# Sheet2.net
KiCad netlist of a schematic drawn in Altium Designer
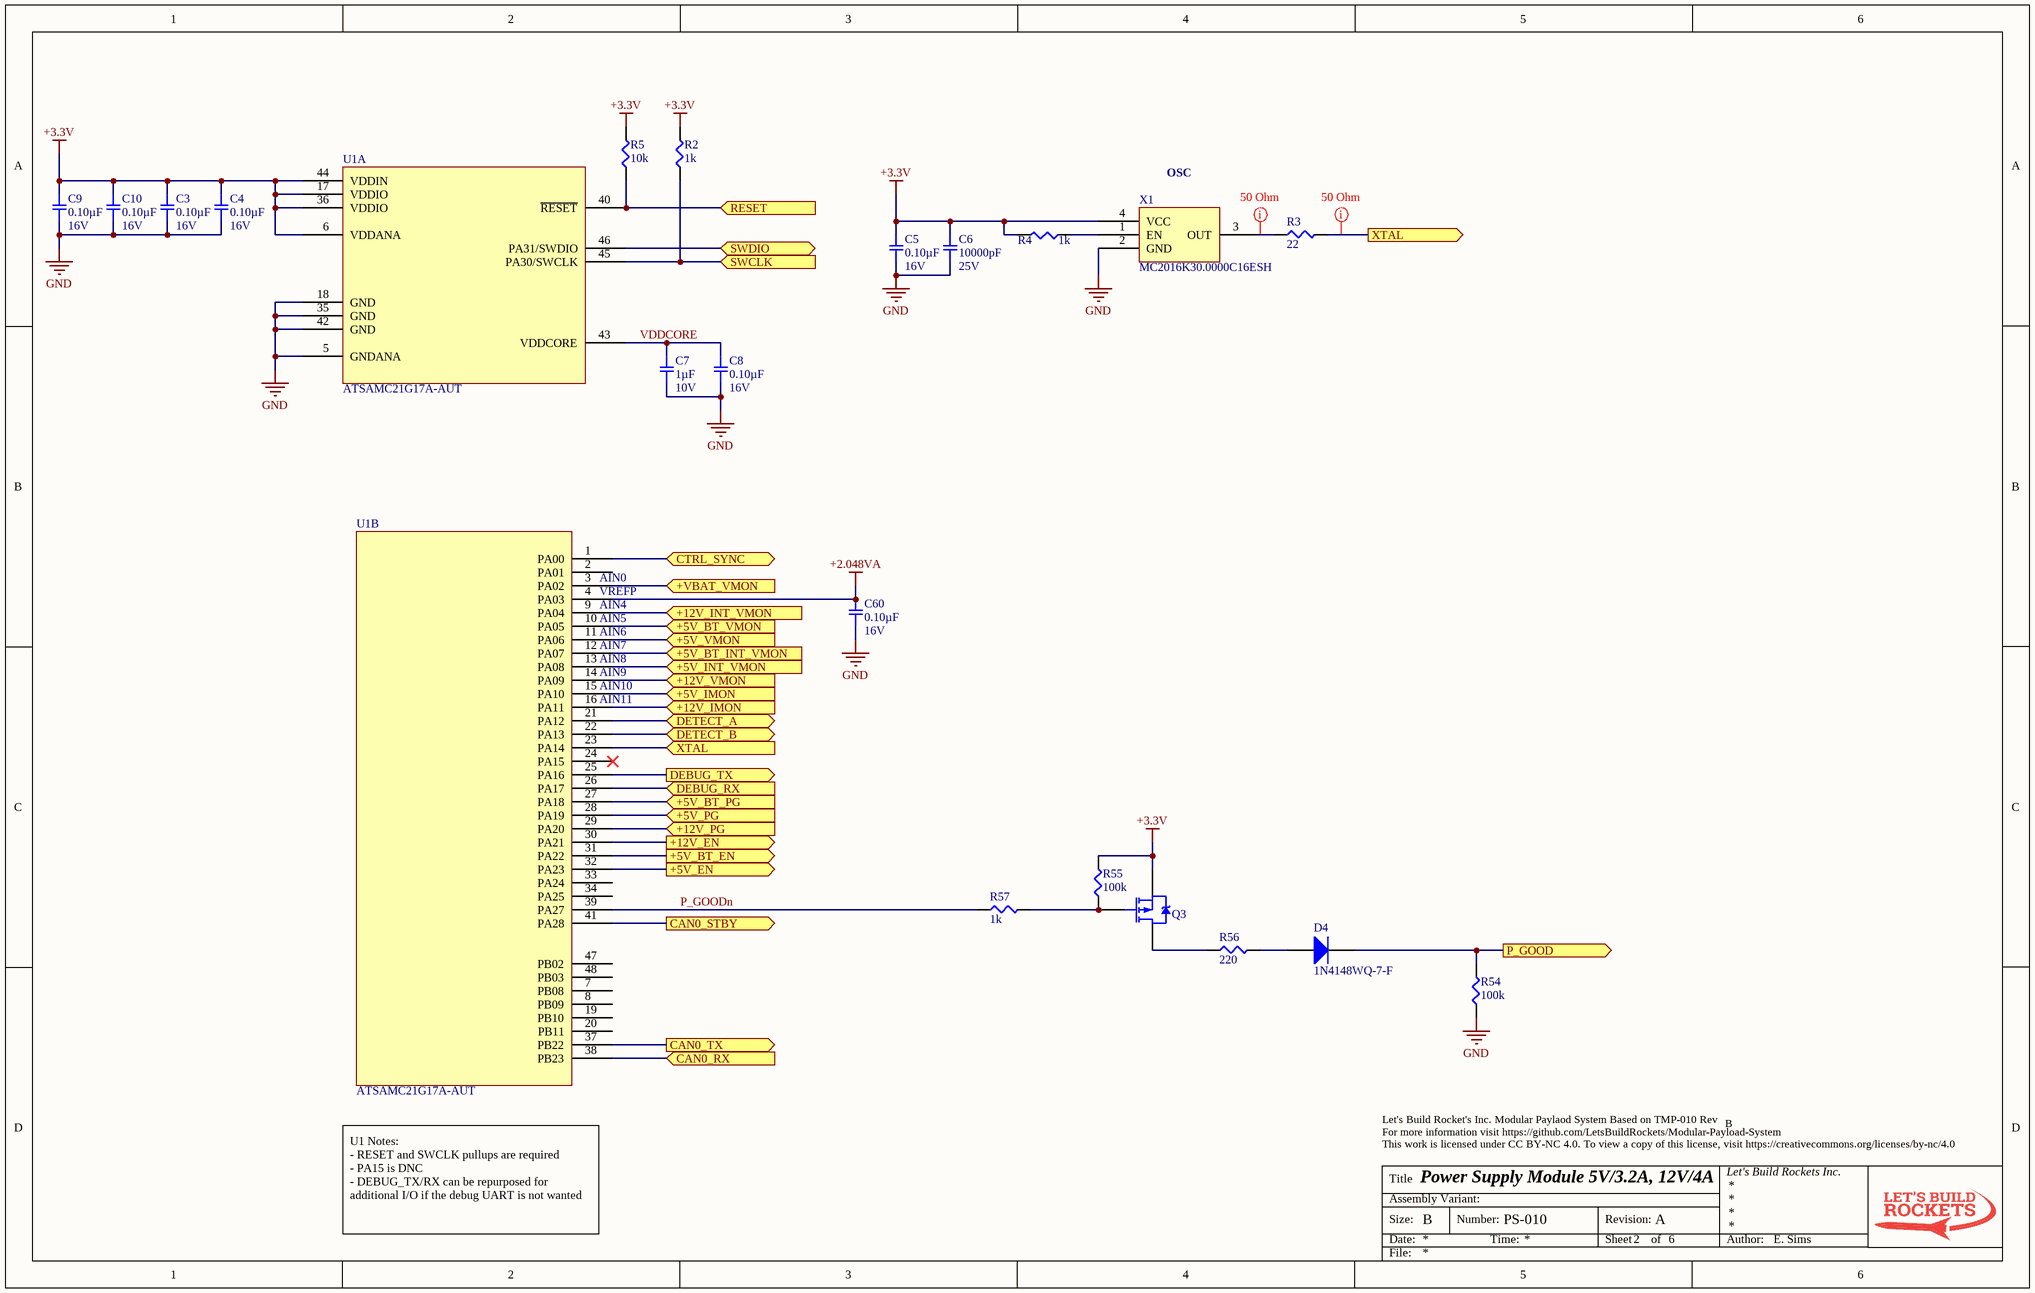
[diagram p0: Sheet2.SchDoc]

(export (version "E")
  (design (tool "Eeschema 10.0.6"))
  (components
    (comp (ref "C3")
      (value "0.10µF")
      (footprint "SMD-0402C")
      (description "CAP CER 0.1UF 16V X7R 0402")
      (fields
        (field (name "DIGI-KEY PART NUMBER") "490-4759-1-ND")
        (field (name "PART NUMBER") "GCM155R71C104KA55D")
        (field (name "VOLTAGE") "16V")
      )
      (libsource (lib "capacitor_murata_0402") (part "GCM155R71C104KA55D"))
    )
    (comp (ref "C4")
      (value "0.10µF")
      (footprint "SMD-0402C")
      (description "CAP CER 0.1UF 16V X7R 0402")
      (fields
        (field (name "DIGI-KEY PART NUMBER") "490-4759-1-ND")
        (field (name "PART NUMBER") "GCM155R71C104KA55D")
        (field (name "VOLTAGE") "16V")
      )
      (libsource (lib "capacitor_murata_0402") (part "GCM155R71C104KA55D"))
    )
    (comp (ref "C5")
      (value "0.10µF")
      (footprint "SMD-0402C")
      (description "CAP CER 0.1UF 16V X7R 0402")
      (fields
        (field (name "DIGI-KEY PART NUMBER") "490-4759-1-ND")
        (field (name "PART NUMBER") "GCM155R71C104KA55D")
        (field (name "VOLTAGE") "16V")
      )
      (libsource (lib "capacitor_murata_0402") (part "GCM155R71C104KA55D"))
    )
    (comp (ref "C6")
      (value "10000pF")
      (footprint "SMD-0402C")
      (description "CAP CER 10000PF 25V X7R 0402")
      (fields
        (field (name "DIGI-KEY PART NUMBER") "490-6043-1-ND")
        (field (name "PART NUMBER") "GCM155R71E103KA37D")
        (field (name "VOLTAGE") "25V")
      )
      (libsource (lib "capacitor_murata_0402") (part "GCM155R71E103KA37D"))
    )
    (comp (ref "C7")
      (value "1µF")
      (footprint "SMD-0402C")
      (description "CAP CER 1UF 10V X7S 0402")
      (fields
        (field (name "DIGI-KEY PART NUMBER") "490-13409-1-ND")
        (field (name "PART NUMBER") "GCM155C71A105KE38D")
        (field (name "VOLTAGE") "10V")
      )
      (libsource (lib "capacitor_murata_0402") (part "GCM155C71A105KE38D"))
    )
    (comp (ref "C8")
      (value "0.10µF")
      (footprint "SMD-0402C")
      (description "CAP CER 0.1UF 16V X7R 0402")
      (fields
        (field (name "DIGI-KEY PART NUMBER") "490-4759-1-ND")
        (field (name "PART NUMBER") "GCM155R71C104KA55D")
        (field (name "VOLTAGE") "16V")
      )
      (libsource (lib "capacitor_murata_0402") (part "GCM155R71C104KA55D"))
    )
    (comp (ref "C9")
      (value "0.10µF")
      (footprint "SMD-0402C")
      (description "CAP CER 0.1UF 16V X7R 0402")
      (fields
        (field (name "DIGI-KEY PART NUMBER") "490-4759-1-ND")
        (field (name "PART NUMBER") "GCM155R71C104KA55D")
        (field (name "VOLTAGE") "16V")
      )
      (libsource (lib "capacitor_murata_0402") (part "GCM155R71C104KA55D"))
    )
    (comp (ref "C10")
      (value "0.10µF")
      (footprint "SMD-0402C")
      (description "CAP CER 0.1UF 16V X7R 0402")
      (fields
        (field (name "DIGI-KEY PART NUMBER") "490-4759-1-ND")
        (field (name "PART NUMBER") "GCM155R71C104KA55D")
        (field (name "VOLTAGE") "16V")
      )
      (libsource (lib "capacitor_murata_0402") (part "GCM155R71C104KA55D"))
    )
    (comp (ref "C60")
      (value "0.10µF")
      (footprint "SMD-0402C")
      (description "CAP CER 0.1UF 16V X7R 0402")
      (fields
        (field (name "DIGI-KEY PART NUMBER") "490-4759-1-ND")
        (field (name "PART NUMBER") "GCM155R71C104KA55D")
        (field (name "VOLTAGE") "16V")
      )
      (libsource (lib "capacitor_murata_0402") (part "GCM155R71C104KA55D"))
    )
    (comp (ref "D4")
      (value "1N4148WQ-7-F")
      (footprint "SOD123")
      (libsource (lib "ModularPayload") (part "1N4148WQ-7-F"))
    )
    (comp (ref "Q3")
      (value "BSS84AK,215")
      (footprint "SOT95P230X110-3N (BSS84)")
      (libsource (lib "ModularPayload") (part "BSS84AK,215"))
    )
    (comp (ref "R2")
      (value "1k")
      (footprint "SMD-0402-RES")
      (description "RES SMD 1K OHM 5% 1/10W 0402")
      (fields (field (name "PART NUMBER") "ERJ-2GEJ102X") (field (name "DIGI-KEY PART NUMBER") "P1.0KJCT-ND"))
      (libsource (lib "Panasonic_ERJ_0402") (part "ERJ-2GEJ102X"))
    )
    (comp (ref "R3")
      (value "22")
      (footprint "SMD-0402-RES")
      (description "RES SMD 22 OHM 1% 1/10W 0402")
      (fields
        (field (name "PART NUMBER") "ERJ-2RKF22R0X")
        (field (name "DIGI-KEY PART NUMBER") "P22.0LCT-ND")
      )
      (libsource (lib "Panasonic_ERJ_0402") (part "ERJ-2RKF22R0X"))
    )
    (comp (ref "R4")
      (value "1k")
      (footprint "SMD-0402-RES")
      (description "RES SMD 1K OHM 5% 1/10W 0402")
      (fields (field (name "PART NUMBER") "ERJ-2GEJ102X") (field (name "DIGI-KEY PART NUMBER") "P1.0KJCT-ND"))
      (libsource (lib "Panasonic_ERJ_0402") (part "ERJ-2GEJ102X"))
    )
    (comp (ref "R5")
      (value "10k")
      (footprint "SMD-0402-RES")
      (description "RES SMD 10K OHM 5% 1/10W 0402")
      (fields (field (name "PART NUMBER") "ERJ-2GEJ103X") (field (name "DIGI-KEY PART NUMBER") "P10KJCT-ND"))
      (libsource (lib "Panasonic_ERJ_0402") (part "ERJ-2GEJ103X"))
    )
    (comp (ref "R54")
      (value "100k")
      (footprint "SMD-0402-RES")
      (description "RES SMD 100K OHM 5% 1/10W 0402")
      (fields (field (name "PART NUMBER") "ERJ-2GEJ104X") (field (name "DIGI-KEY PART NUMBER") "P100KJCT-ND"))
      (libsource (lib "Panasonic_ERJ_0402") (part "ERJ-2GEJ104X"))
    )
    (comp (ref "R55")
      (value "100k")
      (footprint "SMD-0402-RES")
      (description "RES SMD 100K OHM 5% 1/10W 0402")
      (fields (field (name "PART NUMBER") "ERJ-2GEJ104X") (field (name "DIGI-KEY PART NUMBER") "P100KJCT-ND"))
      (libsource (lib "Panasonic_ERJ_0402") (part "ERJ-2GEJ104X"))
    )
    (comp (ref "R56")
      (value "220")
      (footprint "SMD-0402-RES")
      (description "RES SMD 220 OHM 5% 1/10W 0402")
      (fields (field (name "PART NUMBER") "ERJ-2GEJ221X") (field (name "DIGI-KEY PART NUMBER") "P220JCT-ND"))
      (libsource (lib "Panasonic_ERJ_0402") (part "ERJ-2GEJ221X"))
    )
    (comp (ref "R57")
      (value "1k")
      (footprint "SMD-0402-RES")
      (description "RES SMD 1K OHM 5% 1/10W 0402")
      (fields (field (name "PART NUMBER") "ERJ-2GEJ102X") (field (name "DIGI-KEY PART NUMBER") "P1.0KJCT-ND"))
      (libsource (lib "Panasonic_ERJ_0402") (part "ERJ-2GEJ102X"))
    )
    (comp (ref "U1")
      (value "ATSAMC21G17A-AUT")
      (footprint "TSQFP50P900X900X120-48N")
      (libsource (lib "ModularPayload") (part "ATSAMC21G17A-AUT"))
    )
    (comp (ref "X1")
      (value "MC2016K30.0000C16ESH")
      (footprint "MC2016")
      (libsource (lib "ModularPayload") (part "MC2016K30.0000C16ESH"))
    )
  )
  (nets
    (net (code "1") (name "+2.048VA") (class "Default")
      (node (ref "C60") (pin "2") (pinfunction "2_2") (pintype "passive"))
      (node (ref "U1") (pin "4") (pinfunction "PA03_4") (pintype "passive"))
    )
    (net (code "2") (name "+3.3V") (class "Default")
      (node (ref "C10") (pin "2") (pinfunction "2_2") (pintype "passive"))
      (node (ref "C3") (pin "2") (pinfunction "2_2") (pintype "passive"))
      (node (ref "C4") (pin "2") (pinfunction "2_2") (pintype "passive"))
      (node (ref "C5") (pin "2") (pinfunction "2_2") (pintype "passive"))
      (node (ref "C6") (pin "2") (pinfunction "2_2") (pintype "passive"))
      (node (ref "C9") (pin "2") (pinfunction "2_2") (pintype "passive"))
      (node (ref "Q3") (pin "S") (pinfunction "S_S") (pintype "passive"))
      (node (ref "R2") (pin "2") (pinfunction "2_2") (pintype "passive"))
      (node (ref "R4") (pin "2") (pinfunction "2_2") (pintype "passive"))
      (node (ref "R5") (pin "2") (pinfunction "2_2") (pintype "passive"))
      (node (ref "R55") (pin "2") (pinfunction "2_2") (pintype "passive"))
      (node (ref "U1") (pin "17") (pinfunction "VDDIO_17") (pintype "passive"))
      (node (ref "U1") (pin "36") (pinfunction "VDDIO_36") (pintype "passive"))
      (node (ref "U1") (pin "44") (pinfunction "VDDIN_44") (pintype "passive"))
      (node (ref "U1") (pin "6") (pinfunction "VDDANA_6") (pintype "passive"))
      (node (ref "X1") (pin "4") (pinfunction "VCC_4") (pintype "passive"))
    )
    (net (code "3") (name "/+5V_BT_EN") (class "Default")
      (node (ref "U1") (pin "31") (pinfunction "PA22_31") (pintype "passive"))
    )
    (net (code "4") (name "/+5V_BT_INT_VMON") (class "Default")
      (node (ref "U1") (pin "12") (pinfunction "PA07_12") (pintype "passive"))
    )
    (net (code "5") (name "/+5V_BT_PG") (class "Default")
      (node (ref "U1") (pin "27") (pinfunction "PA18_27") (pintype "passive"))
    )
    (net (code "6") (name "/+5V_BT_VMON") (class "Default")
      (node (ref "U1") (pin "10") (pinfunction "PA05_10") (pintype "passive"))
    )
    (net (code "7") (name "/+5V_EN") (class "Default")
      (node (ref "U1") (pin "32") (pinfunction "PA23_32") (pintype "passive"))
    )
    (net (code "8") (name "/+5V_IMON") (class "Default")
      (node (ref "U1") (pin "15") (pinfunction "PA10_15") (pintype "passive"))
    )
    (net (code "9") (name "/+5V_INT_VMON") (class "Default")
      (node (ref "U1") (pin "13") (pinfunction "PA08_13") (pintype "passive"))
    )
    (net (code "10") (name "/+5V_PG") (class "Default")
      (node (ref "U1") (pin "28") (pinfunction "PA19_28") (pintype "passive"))
    )
    (net (code "11") (name "/+5V_VMON") (class "Default")
      (node (ref "U1") (pin "11") (pinfunction "PA06_11") (pintype "passive"))
    )
    (net (code "12") (name "/+12V_EN") (class "Default")
      (node (ref "U1") (pin "30") (pinfunction "PA21_30") (pintype "passive"))
    )
    (net (code "13") (name "/+12V_IMON") (class "Default")
      (node (ref "U1") (pin "16") (pinfunction "PA11_16") (pintype "passive"))
    )
    (net (code "14") (name "/+12V_INT_VMON") (class "Default")
      (node (ref "U1") (pin "9") (pinfunction "PA04_9") (pintype "passive"))
    )
    (net (code "15") (name "/+12V_PG") (class "Default")
      (node (ref "U1") (pin "29") (pinfunction "PA20_29") (pintype "passive"))
    )
    (net (code "16") (name "/+12V_VMON") (class "Default")
      (node (ref "U1") (pin "14") (pinfunction "PA09_14") (pintype "passive"))
    )
    (net (code "17") (name "/+VBAT_VMON") (class "Default")
      (node (ref "U1") (pin "3") (pinfunction "PA02_3") (pintype "passive"))
    )
    (net (code "18") (name "/CAN0_RX") (class "Default")
      (node (ref "U1") (pin "38") (pinfunction "PB23_38") (pintype "passive"))
    )
    (net (code "19") (name "/CAN0_STBY") (class "Default")
      (node (ref "U1") (pin "41") (pinfunction "PA28_41") (pintype "passive"))
    )
    (net (code "20") (name "/CAN0_TX") (class "Default")
      (node (ref "U1") (pin "37") (pinfunction "PB22_37") (pintype "passive"))
    )
    (net (code "21") (name "/CTRL_SYNC") (class "Default")
      (node (ref "U1") (pin "1") (pinfunction "PA00_1") (pintype "passive"))
    )
    (net (code "22") (name "/DEBUG_RX") (class "Default")
      (node (ref "U1") (pin "26") (pinfunction "PA17_26") (pintype "passive"))
    )
    (net (code "23") (name "/DEBUG_TX") (class "Default")
      (node (ref "U1") (pin "25") (pinfunction "PA16_25") (pintype "passive"))
    )
    (net (code "24") (name "/DETECT_A") (class "Default")
      (node (ref "U1") (pin "21") (pinfunction "PA12_21") (pintype "passive"))
    )
    (net (code "25") (name "/DETECT_B") (class "Default")
      (node (ref "U1") (pin "22") (pinfunction "PA13_22") (pintype "passive"))
    )
    (net (code "26") (name "/P_GOOD") (class "Default")
      (node (ref "D4") (pin "K") (pinfunction "K_K") (pintype "passive"))
      (node (ref "R54") (pin "2") (pinfunction "2_2") (pintype "passive"))
    )
    (net (code "27") (name "/P_GOODn") (class "Default")
      (node (ref "R57") (pin "1") (pinfunction "1_1") (pintype "passive"))
      (node (ref "U1") (pin "39") (pinfunction "PA27_39") (pintype "passive"))
    )
    (net (code "28") (name "/RESET") (class "Default")
      (node (ref "R5") (pin "1") (pinfunction "1_1") (pintype "passive"))
      (node (ref "U1") (pin "40") (pinfunction "~{RESET}_40") (pintype "passive"))
    )
    (net (code "29") (name "/SWCLK") (class "Default")
      (node (ref "R2") (pin "1") (pinfunction "1_1") (pintype "passive"))
      (node (ref "U1") (pin "45") (pinfunction "PA30/SWCLK_45") (pintype "passive"))
    )
    (net (code "30") (name "/SWDIO") (class "Default")
      (node (ref "U1") (pin "46") (pinfunction "PA31/SWDIO_46") (pintype "passive"))
    )
    (net (code "31") (name "/VDDCORE") (class "Default")
      (node (ref "C7") (pin "2") (pinfunction "2_2") (pintype "passive"))
      (node (ref "C8") (pin "2") (pinfunction "2_2") (pintype "passive"))
      (node (ref "U1") (pin "43") (pinfunction "VDDCORE_43") (pintype "passive"))
    )
    (net (code "32") (name "/XTAL") (class "Default")
      (node (ref "R3") (pin "2") (pinfunction "2_2") (pintype "passive"))
      (node (ref "U1") (pin "23") (pinfunction "PA14_23") (pintype "passive"))
    )
    (net (code "33") (name "GND") (class "Default")
      (node (ref "C10") (pin "1") (pinfunction "1_1") (pintype "passive"))
      (node (ref "C3") (pin "1") (pinfunction "1_1") (pintype "passive"))
      (node (ref "C4") (pin "1") (pinfunction "1_1") (pintype "passive"))
      (node (ref "C5") (pin "1") (pinfunction "1_1") (pintype "passive"))
      (node (ref "C6") (pin "1") (pinfunction "1_1") (pintype "passive"))
      (node (ref "C60") (pin "1") (pinfunction "1_1") (pintype "passive"))
      (node (ref "C7") (pin "1") (pinfunction "1_1") (pintype "passive"))
      (node (ref "C8") (pin "1") (pinfunction "1_1") (pintype "passive"))
      (node (ref "C9") (pin "1") (pinfunction "1_1") (pintype "passive"))
      (node (ref "R54") (pin "1") (pinfunction "1_1") (pintype "passive"))
      (node (ref "U1") (pin "18") (pinfunction "GND_18") (pintype "passive"))
      (node (ref "U1") (pin "35") (pinfunction "GND_35") (pintype "passive"))
      (node (ref "U1") (pin "42") (pinfunction "GND_42") (pintype "passive"))
      (node (ref "U1") (pin "5") (pinfunction "GNDANA_5") (pintype "passive"))
      (node (ref "X1") (pin "2") (pinfunction "GND_2") (pintype "passive"))
    )
    (net (code "34") (name "Net-(D4-PadA)") (class "Default")
      (node (ref "D4") (pin "A") (pinfunction "A_A") (pintype "passive"))
      (node (ref "R56") (pin "2") (pinfunction "2_2") (pintype "passive"))
    )
    (net (code "35") (name "Net-(Q3-PadD)") (class "Default")
      (node (ref "Q3") (pin "D") (pinfunction "D_D") (pintype "passive"))
      (node (ref "R56") (pin "1") (pinfunction "1_1") (pintype "passive"))
    )
    (net (code "36") (name "Net-(Q3-PadG)") (class "Default")
      (node (ref "Q3") (pin "G") (pinfunction "G_G") (pintype "passive"))
      (node (ref "R55") (pin "1") (pinfunction "1_1") (pintype "passive"))
      (node (ref "R57") (pin "2") (pinfunction "2_2") (pintype "passive"))
    )
    (net (code "37") (name "Net-(X1-EN)") (class "Default")
      (node (ref "R4") (pin "1") (pinfunction "1_1") (pintype "passive"))
      (node (ref "X1") (pin "1") (pinfunction "EN_1") (pintype "passive"))
    )
    (net (code "38") (name "Net-(X1-OUT)") (class "Default")
      (node (ref "R3") (pin "1") (pinfunction "1_1") (pintype "passive"))
      (node (ref "X1") (pin "3") (pinfunction "OUT_3") (pintype "passive"))
    )
    (net (code "39") (name "unconnected-(U1B-PA01-Pad2)") (class "Default")
      (node (ref "U1") (pin "2") (pinfunction "PA01_2") (pintype "passive"))
    )
    (net (code "40") (name "unconnected-(U1B-PA15-Pad24)") (class "Default")
      (node (ref "U1") (pin "24") (pinfunction "PA15_24") (pintype "passive+no_connect"))
    )
    (net (code "41") (name "unconnected-(U1B-PA24-Pad33)") (class "Default")
      (node (ref "U1") (pin "33") (pinfunction "PA24_33") (pintype "passive"))
    )
    (net (code "42") (name "unconnected-(U1B-PA25-Pad34)") (class "Default")
      (node (ref "U1") (pin "34") (pinfunction "PA25_34") (pintype "passive"))
    )
    (net (code "43") (name "unconnected-(U1B-PB02-Pad47)") (class "Default")
      (node (ref "U1") (pin "47") (pinfunction "PB02_47") (pintype "passive"))
    )
    (net (code "44") (name "unconnected-(U1B-PB03-Pad48)") (class "Default")
      (node (ref "U1") (pin "48") (pinfunction "PB03_48") (pintype "passive"))
    )
    (net (code "45") (name "unconnected-(U1B-PB08-Pad7)") (class "Default")
      (node (ref "U1") (pin "7") (pinfunction "PB08_7") (pintype "passive"))
    )
    (net (code "46") (name "unconnected-(U1B-PB09-Pad8)") (class "Default")
      (node (ref "U1") (pin "8") (pinfunction "PB09_8") (pintype "passive"))
    )
    (net (code "47") (name "unconnected-(U1B-PB10-Pad19)") (class "Default")
      (node (ref "U1") (pin "19") (pinfunction "PB10_19") (pintype "passive"))
    )
    (net (code "48") (name "unconnected-(U1B-PB11-Pad20)") (class "Default")
      (node (ref "U1") (pin "20") (pinfunction "PB11_20") (pintype "passive"))
    )
  )
)
